# ledstrip-control.net
KiCad netlist of a schematic drawn in EAGLE
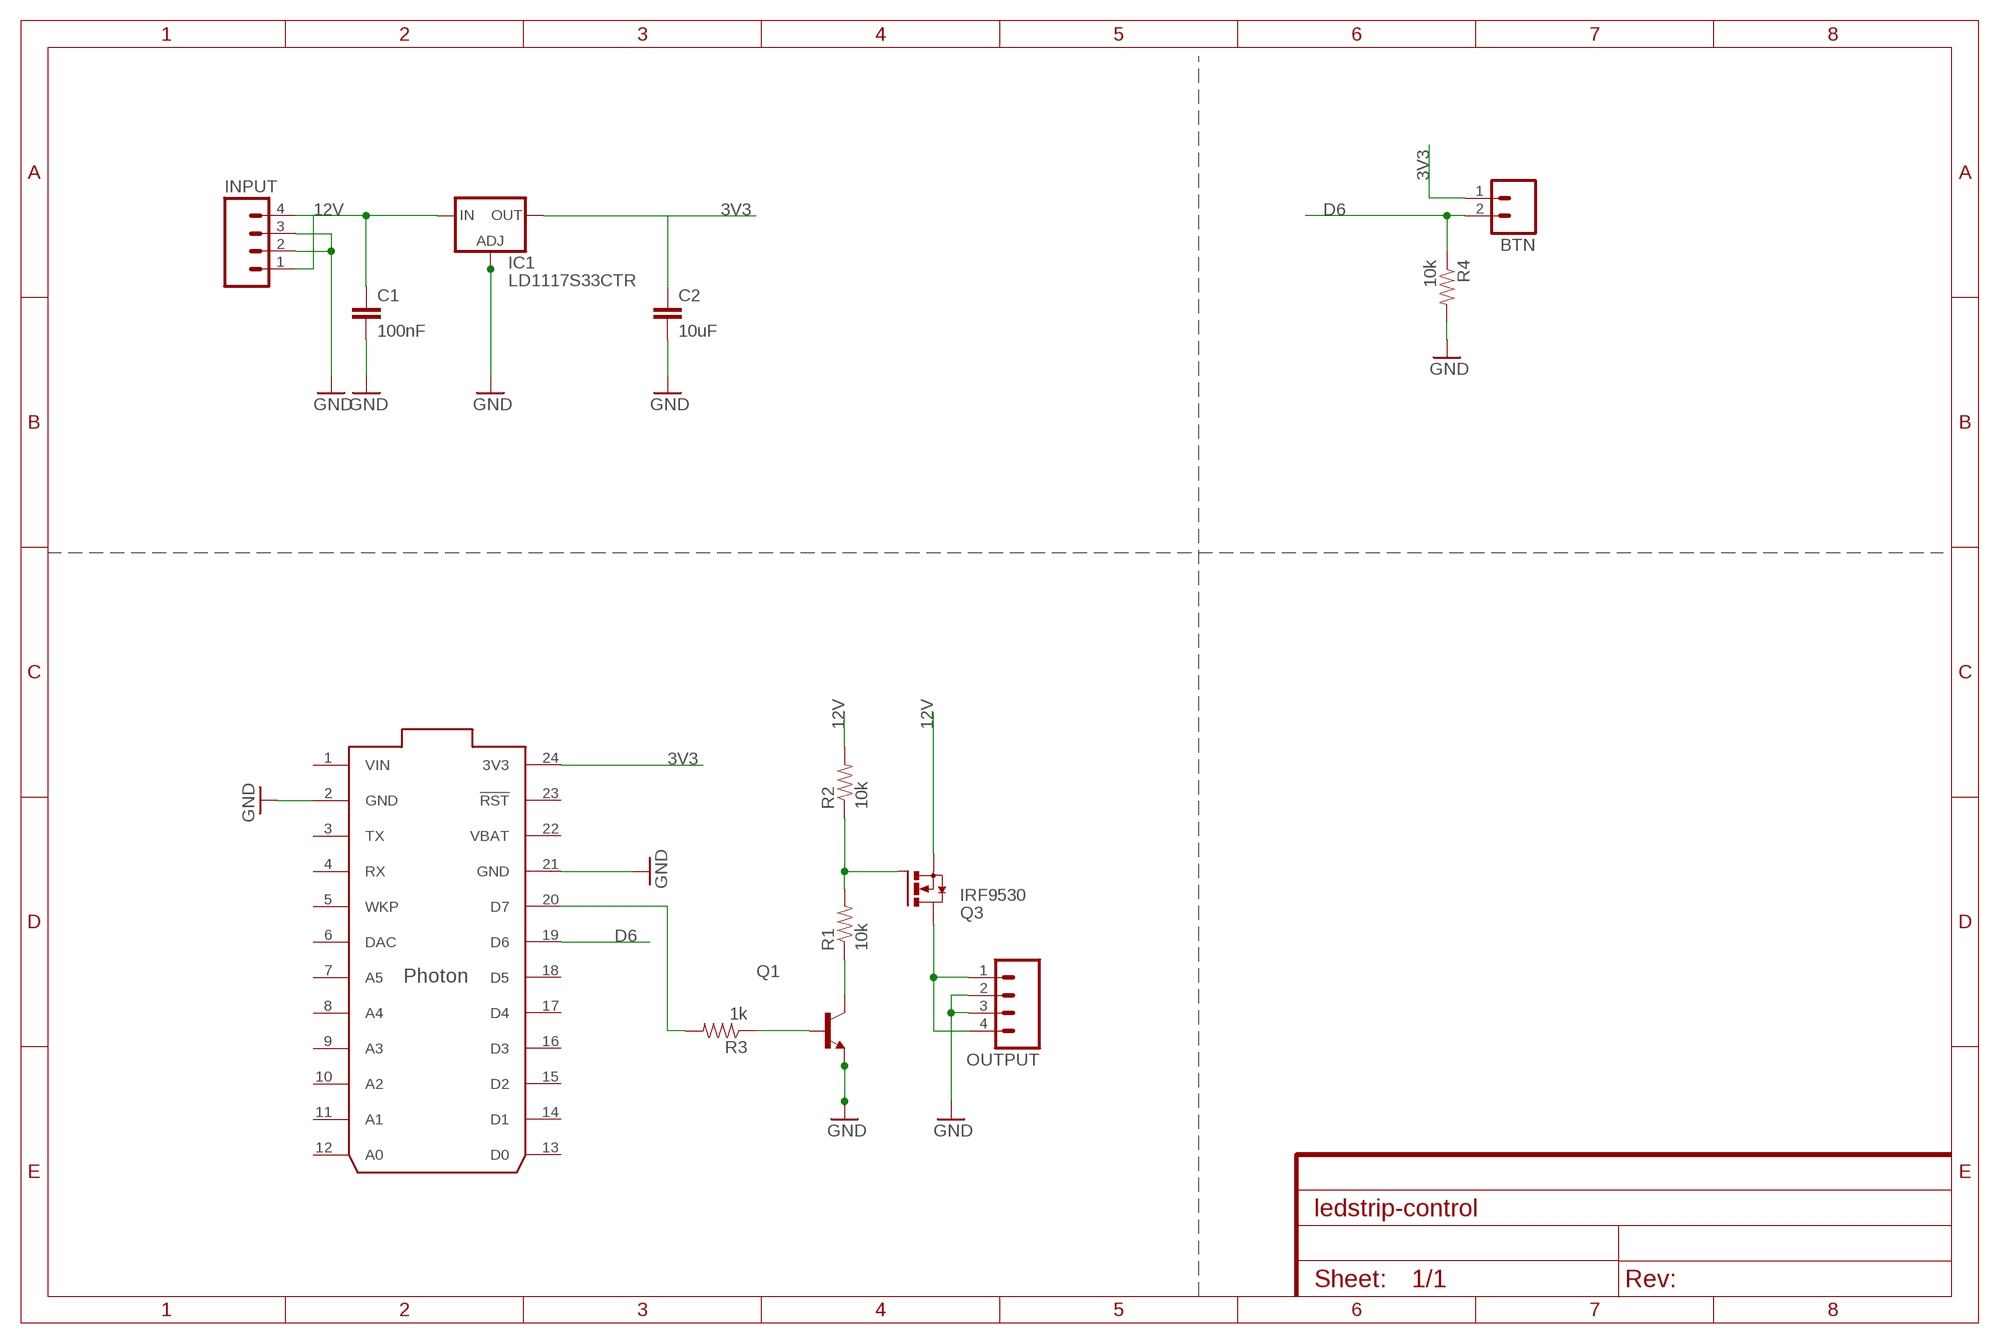
[diagram p0: schematic, sheet 1]

(export (version "E")
  (design (tool "Eeschema 10.0.6"))
  (components
    (comp (ref "BTN")
      (value "M02PTH")
      (footprint "eagle-import:1X02")
      (libsource (lib "eagle-import") (part "M02PTH"))
    )
    (comp (ref "C1")
      (value "100nF")
      (footprint "eagle-import:CAP-PTH-SMALL")
      (libsource (lib "eagle-import") (part "CAPPTH"))
    )
    (comp (ref "C2")
      (value "10uF")
      (footprint "eagle-import:CAP-PTH-SMALL")
      (libsource (lib "eagle-import") (part "CAPPTH"))
    )
    (comp (ref "IC1")
      (value "LD1117S33CTR")
      (footprint "eagle-import:SOT223")
      (libsource (lib "eagle-import") (part "LD117A?S33TR"))
    )
    (comp (ref "INPUT")
      (value "M04PTH")
      (footprint "eagle-import:1X04")
      (libsource (lib "eagle-import") (part "M04PTH"))
    )
    (comp (ref "OUTPUT")
      (value "M04PTH")
      (footprint "eagle-import:1X04")
      (libsource (lib "eagle-import") (part "M04PTH"))
    )
    (comp (ref "Q1")
      (value "2N2222-NPN-TO18-EBC")
      (footprint "eagle-import:TO18")
      (libsource (lib "eagle-import") (part "-NPN-TO18-EBC2N2222"))
    )
    (comp (ref "Q3")
      (value "IRF9530")
      (footprint "eagle-import:D2PACK")
      (libsource (lib "eagle-import") (part "IRF3704S"))
    )
    (comp (ref "R1")
      (value "10k")
      (footprint "eagle-import:AXIAL-0.3")
      (libsource (lib "eagle-import") (part "RESISTORAXIAL-0.3"))
    )
    (comp (ref "R2")
      (value "10k")
      (footprint "eagle-import:AXIAL-0.3")
      (libsource (lib "eagle-import") (part "RESISTORAXIAL-0.3"))
    )
    (comp (ref "R3")
      (value "1k")
      (footprint "eagle-import:AXIAL-0.3")
      (libsource (lib "eagle-import") (part "RESISTORAXIAL-0.3"))
    )
    (comp (ref "R4")
      (value "10k")
      (footprint "eagle-import:AXIAL-0.3")
      (libsource (lib "eagle-import") (part "RESISTORAXIAL-0.3"))
    )
    (comp (ref "U1")
      (value "PHOTON_WITH_HEADERS")
      (footprint "eagle-import:PHOTON")
      (libsource (lib "eagle-import") (part "PHOTON_WITH_HEADERS"))
    )
  )
  (nets
    (net (code "1") (name "/3V3") (class "Default")
      (node (ref "BTN") (pin "1") (pinfunction "1_1") (pintype "passive"))
      (node (ref "C2") (pin "1") (pinfunction "1_1") (pintype "passive"))
      (node (ref "IC1") (pin "4") (pinfunction "OUT_4") (pintype "passive"))
      (node (ref "U1") (pin "24") (pinfunction "3V3_24") (pintype "power_in"))
    )
    (net (code "2") (name "/12V") (class "Default")
      (node (ref "C1") (pin "1") (pinfunction "1_1") (pintype "passive"))
      (node (ref "IC1") (pin "3") (pinfunction "IN_3") (pintype "input"))
      (node (ref "INPUT") (pin "1") (pinfunction "1_1") (pintype "passive"))
      (node (ref "INPUT") (pin "4") (pinfunction "4_4") (pintype "passive"))
      (node (ref "Q3") (pin "3") (pinfunction "S_3") (pintype "passive"))
      (node (ref "R2") (pin "P$2") (pinfunction "2_P$2") (pintype "passive"))
    )
    (net (code "3") (name "/D6") (class "Default")
      (node (ref "BTN") (pin "2") (pinfunction "2_2") (pintype "passive"))
      (node (ref "R4") (pin "P$1") (pinfunction "1_P$1") (pintype "passive"))
      (node (ref "U1") (pin "19") (pinfunction "D6_19") (pintype "bidirectional"))
    )
    (net (code "4") (name "/VBAT") (class "Default")
      (node (ref "U1") (pin "22") (pinfunction "VBAT_22") (pintype "power_in"))
    )
    (net (code "5") (name "/VIN") (class "Default")
      (node (ref "U1") (pin "1") (pinfunction "VIN_1") (pintype "power_in"))
    )
    (net (code "6") (name "GND") (class "Default")
      (node (ref "C1") (pin "2") (pinfunction "2_2") (pintype "passive"))
      (node (ref "C2") (pin "2") (pinfunction "2_2") (pintype "passive"))
      (node (ref "IC1") (pin "1") (pinfunction "ADJ_1") (pintype "input"))
      (node (ref "INPUT") (pin "2") (pinfunction "2_2") (pintype "passive"))
      (node (ref "INPUT") (pin "3") (pinfunction "3_3") (pintype "passive"))
      (node (ref "OUTPUT") (pin "2") (pinfunction "2_2") (pintype "passive"))
      (node (ref "OUTPUT") (pin "3") (pinfunction "3_3") (pintype "passive"))
      (node (ref "Q1") (pin "1") (pinfunction "E_1") (pintype "passive"))
      (node (ref "R4") (pin "P$2") (pinfunction "2_P$2") (pintype "passive"))
      (node (ref "U1") (pin "2") (pinfunction "GND_2") (pintype "power_in"))
      (node (ref "U1") (pin "21") (pinfunction "GND_21") (pintype "power_in"))
    )
    (net (code "7") (name "Net-(Q1-B)") (class "Default")
      (node (ref "Q1") (pin "2") (pinfunction "B_2") (pintype "passive"))
      (node (ref "R3") (pin "P$1") (pinfunction "1_P$1") (pintype "passive"))
    )
    (net (code "8") (name "Net-(Q1-C)") (class "Default")
      (node (ref "Q1") (pin "3") (pinfunction "C_3") (pintype "passive"))
      (node (ref "R1") (pin "P$1") (pinfunction "1_P$1") (pintype "passive"))
    )
    (net (code "9") (name "Net-(Q3-D)") (class "Default")
      (node (ref "OUTPUT") (pin "1") (pinfunction "1_1") (pintype "passive"))
      (node (ref "OUTPUT") (pin "4") (pinfunction "4_4") (pintype "passive"))
      (node (ref "Q3") (pin "2") (pinfunction "D_2") (pintype "passive"))
    )
    (net (code "10") (name "Net-(Q3-G)") (class "Default")
      (node (ref "Q3") (pin "1") (pinfunction "G_1") (pintype "passive"))
      (node (ref "R1") (pin "P$2") (pinfunction "2_P$2") (pintype "passive"))
      (node (ref "R2") (pin "P$1") (pinfunction "1_P$1") (pintype "passive"))
    )
    (net (code "11") (name "Net-(R3-2)") (class "Default")
      (node (ref "R3") (pin "P$2") (pinfunction "2_P$2") (pintype "passive"))
      (node (ref "U1") (pin "20") (pinfunction "D7_20") (pintype "bidirectional"))
    )
    (net (code "12") (name "unconnected-(U1-A0-Pad12)") (class "Default")
      (node (ref "U1") (pin "12") (pinfunction "A0_12") (pintype "bidirectional"))
    )
    (net (code "13") (name "unconnected-(U1-A1-Pad11)") (class "Default")
      (node (ref "U1") (pin "11") (pinfunction "A1_11") (pintype "bidirectional"))
    )
    (net (code "14") (name "unconnected-(U1-A2-Pad10)") (class "Default")
      (node (ref "U1") (pin "10") (pinfunction "A2_10") (pintype "bidirectional"))
    )
    (net (code "15") (name "unconnected-(U1-A3-Pad9)") (class "Default")
      (node (ref "U1") (pin "9") (pinfunction "A3_9") (pintype "bidirectional"))
    )
    (net (code "16") (name "unconnected-(U1-A4-Pad8)") (class "Default")
      (node (ref "U1") (pin "8") (pinfunction "A4_8") (pintype "bidirectional"))
    )
    (net (code "17") (name "unconnected-(U1-A5-Pad7)") (class "Default")
      (node (ref "U1") (pin "7") (pinfunction "A5_7") (pintype "bidirectional"))
    )
    (net (code "18") (name "unconnected-(U1-D0-Pad13)") (class "Default")
      (node (ref "U1") (pin "13") (pinfunction "D0_13") (pintype "bidirectional"))
    )
    (net (code "19") (name "unconnected-(U1-D1-Pad14)") (class "Default")
      (node (ref "U1") (pin "14") (pinfunction "D1_14") (pintype "bidirectional"))
    )
    (net (code "20") (name "unconnected-(U1-D2-Pad15)") (class "Default")
      (node (ref "U1") (pin "15") (pinfunction "D2_15") (pintype "bidirectional"))
    )
    (net (code "21") (name "unconnected-(U1-D3-Pad16)") (class "Default")
      (node (ref "U1") (pin "16") (pinfunction "D3_16") (pintype "bidirectional"))
    )
    (net (code "22") (name "unconnected-(U1-D4-Pad17)") (class "Default")
      (node (ref "U1") (pin "17") (pinfunction "D4_17") (pintype "bidirectional"))
    )
    (net (code "23") (name "unconnected-(U1-D5-Pad18)") (class "Default")
      (node (ref "U1") (pin "18") (pinfunction "D5_18") (pintype "bidirectional"))
    )
    (net (code "24") (name "unconnected-(U1-DAC-Pad6)") (class "Default")
      (node (ref "U1") (pin "6") (pinfunction "DAC_6") (pintype "bidirectional"))
    )
    (net (code "25") (name "unconnected-(U1-RX-Pad4)") (class "Default")
      (node (ref "U1") (pin "4") (pinfunction "RX_4") (pintype "bidirectional"))
    )
    (net (code "26") (name "unconnected-(U1-TX-Pad3)") (class "Default")
      (node (ref "U1") (pin "3") (pinfunction "TX_3") (pintype "bidirectional"))
    )
    (net (code "27") (name "unconnected-(U1-WKP-Pad5)") (class "Default")
      (node (ref "U1") (pin "5") (pinfunction "WKP_5") (pintype "bidirectional"))
    )
    (net (code "28") (name "unconnected-(U1-~{RST}-Pad23)") (class "Default")
      (node (ref "U1") (pin "23") (pinfunction "~{RST}_23") (pintype "bidirectional"))
    )
  )
)
